# TranslatorETH.net
KiCad netlist of a schematic drawn in EAGLE
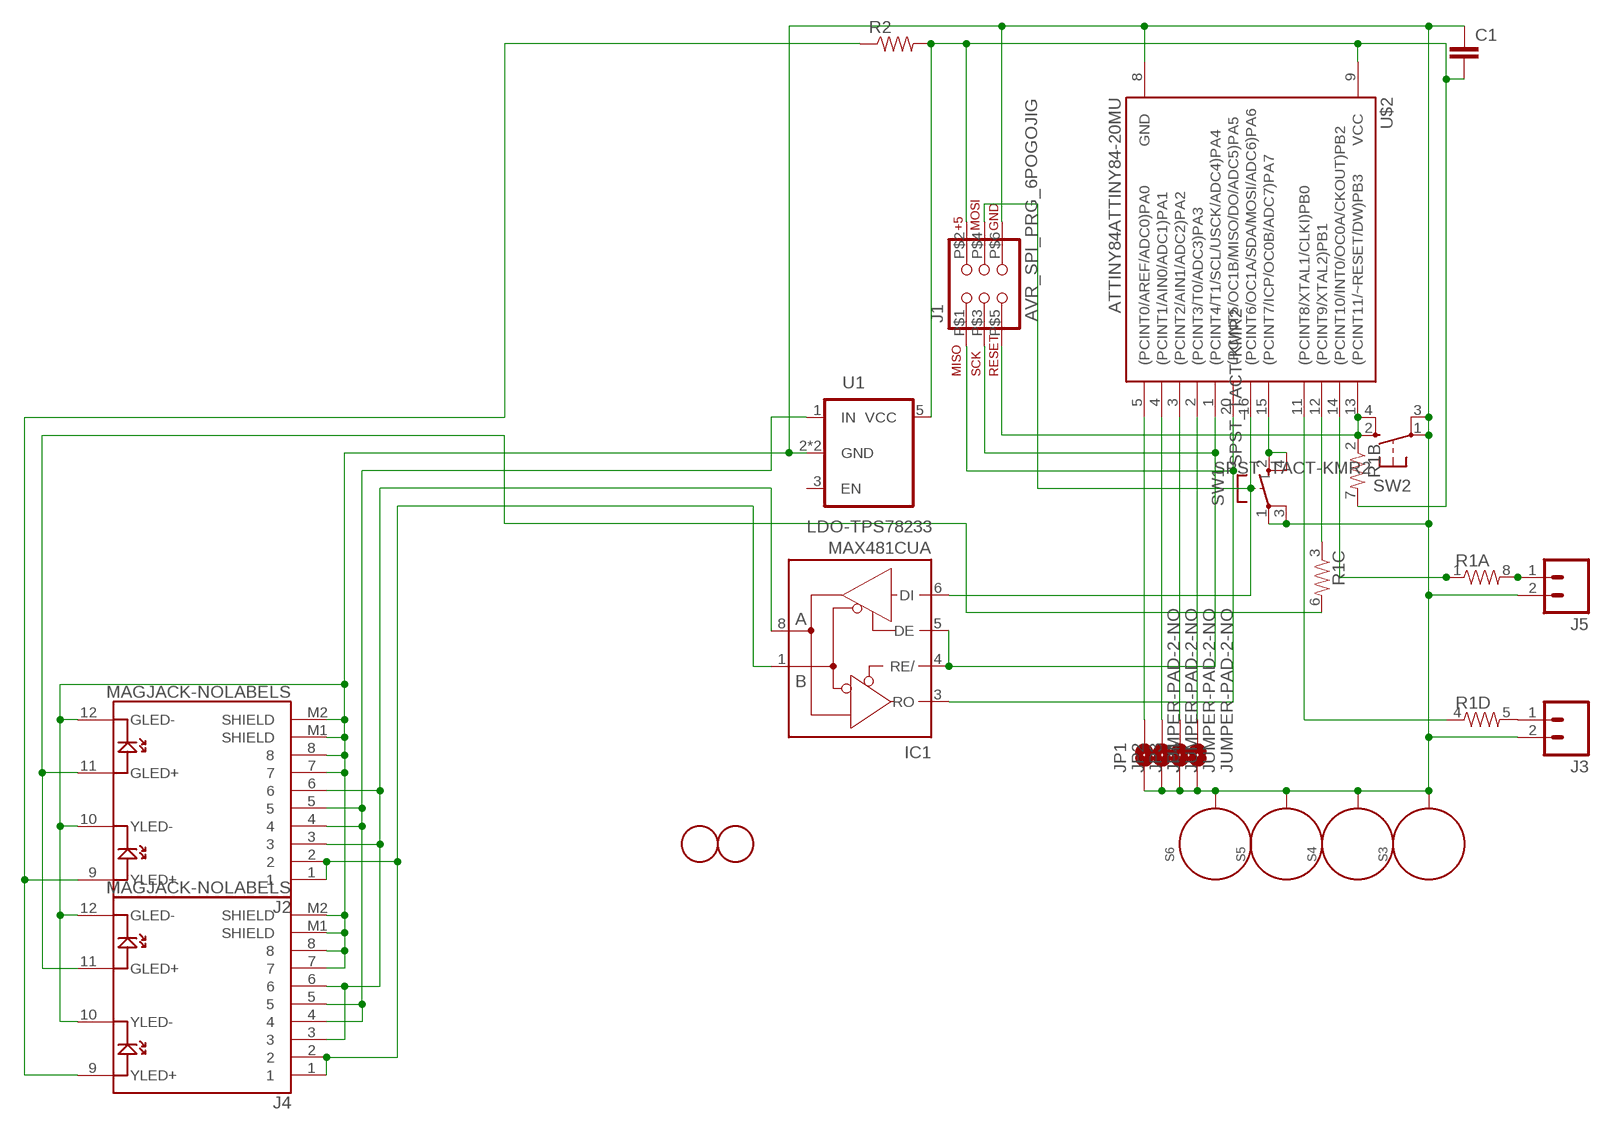
[diagram p0: schematic, sheet 1]

(export (version "E")
  (design (tool "Eeschema 10.0.6"))
  (components
    (comp (ref "C1")
      (value "CAP0805")
      (footprint "eagle-import:0805")
      (libsource (lib "eagle-import") (part "CAP0805"))
    )
    (comp (ref "IC1")
      (value "MAX481CUA")
      (footprint "eagle-import:UMAX8")
      (fields (field (name "MPN") "MAX481CUA+"))
      (libsource (lib "eagle-import") (part "MAX481CUA"))
    )
    (comp (ref "J1")
      (value "AVR_SPI_PRG_6POGOJIG")
      (footprint "eagle-import:2X3_MAX")
      (libsource (lib "eagle-import") (part "AVR_SPI_PRG_6POGOJIG"))
    )
    (comp (ref "J2")
      (value "MAGJACK-NOLABELS")
      (footprint "eagle-import:MAGJACK")
      (libsource (lib "eagle-import") (part "MAGJACK-NOLABELS"))
    )
    (comp (ref "J3")
      (value "M025MM")
      (footprint "eagle-import:SCREWTERMINAL-5MM-2")
      (libsource (lib "eagle-import") (part "M025MM"))
    )
    (comp (ref "J4")
      (value "MAGJACK-NOLABELS")
      (footprint "eagle-import:MAGJACK")
      (libsource (lib "eagle-import") (part "MAGJACK-NOLABELS"))
    )
    (comp (ref "J5")
      (value "M025MM")
      (footprint "eagle-import:SCREWTERMINAL-5MM-2")
      (libsource (lib "eagle-import") (part "M025MM"))
    )
    (comp (ref "JP1")
      (value "JUMPER-PAD-2-NO")
      (footprint "eagle-import:PAD-JUMPER-2-NO_NO_SILK")
      (libsource (lib "eagle-import") (part "JUMPER-PAD-2-NO"))
    )
    (comp (ref "JP2")
      (value "JUMPER-PAD-2-NO")
      (footprint "eagle-import:PAD-JUMPER-2-NO_NO_SILK")
      (libsource (lib "eagle-import") (part "JUMPER-PAD-2-NO"))
    )
    (comp (ref "JP3")
      (value "JUMPER-PAD-2-NO")
      (footprint "eagle-import:PAD-JUMPER-2-NO_NO_SILK")
      (libsource (lib "eagle-import") (part "JUMPER-PAD-2-NO"))
    )
    (comp (ref "JP4")
      (value "JUMPER-PAD-2-NO")
      (footprint "eagle-import:PAD-JUMPER-2-NO_NO_SILK")
      (libsource (lib "eagle-import") (part "JUMPER-PAD-2-NO"))
    )
    (comp (ref "R1")
      (value "RESISTOR-ARRAY0603-ARV")
      (footprint "eagle-import:0603-ARV")
      (libsource (lib "eagle-import") (part "RESISTOR-ARRAY0603-ARV"))
    )
    (comp (ref "R2")
      (value "RESISTOR0805-RES")
      (footprint "eagle-import:0805")
      (libsource (lib "eagle-import") (part "RESISTOR0805-RES"))
    )
    (comp (ref "S3")
      (value "STANDOFF_ELECTRICAL")
      (footprint "eagle-import:STANDOFF-ELECTRICAL")
      (libsource (lib "eagle-import") (part "STANDOFF_ELECTRICAL"))
    )
    (comp (ref "S4")
      (value "STANDOFF_ELECTRICAL")
      (footprint "eagle-import:STANDOFF-ELECTRICAL")
      (libsource (lib "eagle-import") (part "STANDOFF_ELECTRICAL"))
    )
    (comp (ref "S5")
      (value "STANDOFF_ELECTRICAL")
      (footprint "eagle-import:STANDOFF-ELECTRICAL")
      (libsource (lib "eagle-import") (part "STANDOFF_ELECTRICAL"))
    )
    (comp (ref "S6")
      (value "STANDOFF_ELECTRICAL")
      (footprint "eagle-import:STANDOFF-ELECTRICAL")
      (libsource (lib "eagle-import") (part "STANDOFF_ELECTRICAL"))
    )
    (comp (ref "SW1")
      (value "SPST_TACT-KMR2")
      (footprint "eagle-import:KMR2")
      (libsource (lib "eagle-import") (part "SPST_TACT-KMR2"))
    )
    (comp (ref "SW2")
      (value "SPST_TACT-KMR2")
      (footprint "eagle-import:KMR2")
      (libsource (lib "eagle-import") (part "SPST_TACT-KMR2"))
    )
    (comp (ref "U$2")
      (value "ATTINY84ATTINY84-20MU")
      (footprint "eagle-import:QFN20")
      (libsource (lib "eagle-import") (part "ATTINY84ATTINY84-20MU"))
    )
    (comp (ref "U$3")
      (value "FIDUCIAL")
      (footprint "eagle-import:FIDUCIAL_1MM")
      (libsource (lib "eagle-import") (part "FIDUCIAL"))
    )
    (comp (ref "U$4")
      (value "FIDUCIAL")
      (footprint "eagle-import:FIDUCIAL_1MM")
      (libsource (lib "eagle-import") (part "FIDUCIAL"))
    )
    (comp (ref "U1")
      (value "LDO-TPS78233")
      (footprint "eagle-import:SOT23-5")
      (libsource (lib "eagle-import") (part "LDO-TPS78233"))
    )
  )
  (nets
    (net (code "1") (name "Net-(IC1A-A)") (class "Default")
      (node (ref "IC1") (pin "8") (pinfunction "A_8") (pintype "passive"))
      (node (ref "J2") (pin "3") (pinfunction "3_3") (pintype "bidirectional"))
      (node (ref "J2") (pin "6") (pinfunction "6_6") (pintype "bidirectional"))
      (node (ref "J4") (pin "3") (pinfunction "3_3") (pintype "bidirectional"))
      (node (ref "J4") (pin "6") (pinfunction "6_6") (pintype "bidirectional"))
    )
    (net (code "2") (name "Net-(IC1A-B)") (class "Default")
      (node (ref "IC1") (pin "1") (pinfunction "B_1") (pintype "passive"))
      (node (ref "J2") (pin "1") (pinfunction "1_1") (pintype "bidirectional"))
      (node (ref "J2") (pin "2") (pinfunction "2_2") (pintype "bidirectional"))
      (node (ref "J4") (pin "1") (pinfunction "1_1") (pintype "bidirectional"))
      (node (ref "J4") (pin "2") (pinfunction "2_2") (pintype "bidirectional"))
    )
    (net (code "3") (name "Net-(IC1A-DE)") (class "Default")
      (node (ref "IC1") (pin "4") (pinfunction "RE/_4") (pintype "input"))
      (node (ref "IC1") (pin "5") (pinfunction "DE_5") (pintype "input"))
      (node (ref "J1") (pin "P$3") (pinfunction "SCK_P$3") (pintype "passive"))
      (node (ref "U$2") (pin "1") (pinfunction "(PCINT4/T1/SCL/USCK/ADC4)PA4_1") (pintype "bidirectional"))
    )
    (net (code "4") (name "Net-(IC1A-DI)") (class "Default")
      (node (ref "IC1") (pin "6") (pinfunction "DI_6") (pintype "input"))
      (node (ref "J1") (pin "P$4") (pinfunction "MOSI_P$4") (pintype "passive"))
      (node (ref "U$2") (pin "16") (pinfunction "(PCINT6/OC1A/SDA/MOSI/ADC6)PA6_16") (pintype "bidirectional"))
    )
    (net (code "5") (name "Net-(IC1A-RO)") (class "Default")
      (node (ref "IC1") (pin "3") (pinfunction "RO_3") (pintype "output"))
      (node (ref "J1") (pin "P$1") (pinfunction "MISO_P$1") (pintype "passive"))
      (node (ref "U$2") (pin "20") (pinfunction "(PCINT5/OC1B/MISO/DO/ADC5)PA5_20") (pintype "bidirectional"))
    )
    (net (code "6") (name "Net-(J1-GND)") (class "Default")
      (node (ref "C1") (pin "1") (pinfunction "1_1") (pintype "passive"))
      (node (ref "J1") (pin "P$6") (pinfunction "GND_P$6") (pintype "passive"))
      (node (ref "J2") (pin "10") (pinfunction "YLED-_10") (pintype "bidirectional"))
      (node (ref "J2") (pin "12") (pinfunction "GLED-_12") (pintype "bidirectional"))
      (node (ref "J2") (pin "7") (pinfunction "7_7") (pintype "bidirectional"))
      (node (ref "J2") (pin "8") (pinfunction "8_8") (pintype "bidirectional"))
      (node (ref "J2") (pin "M1") (pinfunction "SHIELD_M1") (pintype "bidirectional"))
      (node (ref "J2") (pin "M2") (pinfunction "SHIELD_M2") (pintype "bidirectional"))
      (node (ref "J3") (pin "2") (pinfunction "2_2") (pintype "passive"))
      (node (ref "J4") (pin "10") (pinfunction "YLED-_10") (pintype "bidirectional"))
      (node (ref "J4") (pin "12") (pinfunction "GLED-_12") (pintype "bidirectional"))
      (node (ref "J4") (pin "7") (pinfunction "7_7") (pintype "bidirectional"))
      (node (ref "J4") (pin "8") (pinfunction "8_8") (pintype "bidirectional"))
      (node (ref "J4") (pin "M1") (pinfunction "SHIELD_M1") (pintype "bidirectional"))
      (node (ref "J4") (pin "M2") (pinfunction "SHIELD_M2") (pintype "bidirectional"))
      (node (ref "J5") (pin "2") (pinfunction "2_2") (pintype "passive"))
      (node (ref "JP1") (pin "1") (pinfunction "1_1") (pintype "passive"))
      (node (ref "JP2") (pin "1") (pinfunction "1_1") (pintype "passive"))
      (node (ref "JP3") (pin "1") (pinfunction "1_1") (pintype "passive"))
      (node (ref "JP4") (pin "1") (pinfunction "1_1") (pintype "passive"))
      (node (ref "S3") (pin "P1") (pinfunction "P$1_P1") (pintype "bidirectional"))
      (node (ref "S4") (pin "P1") (pinfunction "P$1_P1") (pintype "bidirectional"))
      (node (ref "S5") (pin "P1") (pinfunction "P$1_P1") (pintype "bidirectional"))
      (node (ref "S6") (pin "P1") (pinfunction "P$1_P1") (pintype "bidirectional"))
      (node (ref "SW1") (pin "1") (pinfunction "P_1") (pintype "passive"))
      (node (ref "SW1") (pin "3") (pinfunction "P1_3") (pintype "passive"))
      (node (ref "SW2") (pin "1") (pinfunction "P_1") (pintype "passive"))
      (node (ref "SW2") (pin "3") (pinfunction "P1_3") (pintype "passive"))
      (node (ref "U$2") (pin "8") (pinfunction "GND_8") (pintype "bidirectional"))
      (node (ref "U1") (pin "2") (pinfunction "GND_2") (pintype "input"))
      (node (ref "U1") (pin "4") (pinfunction "GND_4") (pintype "input"))
    )
    (net (code "7") (name "Net-(J1-RESET)") (class "Default")
      (node (ref "J1") (pin "P$5") (pinfunction "RESET_P$5") (pintype "passive"))
      (node (ref "R1") (pin "2") (pinfunction "1_2") (pintype "passive"))
      (node (ref "SW2") (pin "2") (pinfunction "S_2") (pintype "passive"))
      (node (ref "SW2") (pin "4") (pinfunction "S1_4") (pintype "passive"))
      (node (ref "U$2") (pin "13") (pinfunction "(PCINT11/~{RESET/DW})PB3_13") (pintype "bidirectional"))
    )
    (net (code "8") (name "Net-(J1-VIN)") (class "Default")
      (node (ref "C1") (pin "2") (pinfunction "2_2") (pintype "passive"))
      (node (ref "J1") (pin "P$2") (pinfunction "VIN_P$2") (pintype "passive"))
      (node (ref "R1") (pin "7") (pinfunction "2_7") (pintype "passive"))
      (node (ref "R2") (pin "2") (pinfunction "2_2") (pintype "passive"))
      (node (ref "U$2") (pin "9") (pinfunction "VCC_9") (pintype "bidirectional"))
      (node (ref "U1") (pin "5") (pinfunction "VCC_5") (pintype "power_in"))
    )
    (net (code "9") (name "Net-(J2-GLED+)") (class "Default")
      (node (ref "J2") (pin "11") (pinfunction "GLED+_11") (pintype "bidirectional"))
      (node (ref "J4") (pin "11") (pinfunction "GLED+_11") (pintype "bidirectional"))
      (node (ref "R1") (pin "6") (pinfunction "2_6") (pintype "passive"))
    )
    (net (code "10") (name "Net-(J2-YLED+)") (class "Default")
      (node (ref "J2") (pin "9") (pinfunction "YLED+_9") (pintype "bidirectional"))
      (node (ref "J4") (pin "9") (pinfunction "YLED+_9") (pintype "bidirectional"))
      (node (ref "R2") (pin "1") (pinfunction "1_1") (pintype "passive"))
    )
    (net (code "11") (name "Net-(R1A-2)") (class "Default")
      (node (ref "J5") (pin "1") (pinfunction "1_1") (pintype "passive"))
      (node (ref "R1") (pin "8") (pinfunction "2_8") (pintype "passive"))
    )
    (net (code "12") (name "Net-(R1C-1)") (class "Default")
      (node (ref "R1") (pin "3") (pinfunction "1_3") (pintype "passive"))
      (node (ref "U$2") (pin "12") (pinfunction "(PCINT9/XTAL2)PB1_12") (pintype "bidirectional"))
    )
    (net (code "13") (name "Net-(R1D-1)") (class "Default")
      (node (ref "R1") (pin "4") (pinfunction "1_4") (pintype "passive"))
      (node (ref "U$2") (pin "11") (pinfunction "(PCINT8/XTAL1/CLKI)PB0_11") (pintype "bidirectional"))
    )
    (net (code "14") (name "Net-(R1D-2)") (class "Default")
      (node (ref "J3") (pin "1") (pinfunction "1_1") (pintype "passive"))
      (node (ref "R1") (pin "5") (pinfunction "2_5") (pintype "passive"))
    )
    (net (code "15") (name "Net-(SW1-S)") (class "Default")
      (node (ref "SW1") (pin "2") (pinfunction "S_2") (pintype "passive"))
      (node (ref "SW1") (pin "4") (pinfunction "S1_4") (pintype "passive"))
      (node (ref "U$2") (pin "15") (pinfunction "(PCINT7/ICP/OC0B/ADC7)PA7_15") (pintype "bidirectional"))
    )
    (net (code "16") (name "Net-(U$2-(PCINT0{slash}AREF{slash}ADC0)PA0)") (class "Default")
      (node (ref "JP1") (pin "2") (pinfunction "2_2") (pintype "passive"))
      (node (ref "U$2") (pin "5") (pinfunction "(PCINT0/AREF/ADC0)PA0_5") (pintype "bidirectional"))
    )
    (net (code "17") (name "Net-(U$2-(PCINT1{slash}AIN0{slash}ADC1)PA1)") (class "Default")
      (node (ref "JP2") (pin "2") (pinfunction "2_2") (pintype "passive"))
      (node (ref "U$2") (pin "4") (pinfunction "(PCINT1/AIN0/ADC1)PA1_4") (pintype "bidirectional"))
    )
    (net (code "18") (name "Net-(U$2-(PCINT2{slash}AIN1{slash}ADC2)PA2)") (class "Default")
      (node (ref "JP3") (pin "2") (pinfunction "2_2") (pintype "passive"))
      (node (ref "U$2") (pin "3") (pinfunction "(PCINT2/AIN1/ADC2)PA2_3") (pintype "bidirectional"))
    )
    (net (code "19") (name "Net-(U$2-(PCINT3{slash}T0{slash}ADC3)PA3)") (class "Default")
      (node (ref "JP4") (pin "2") (pinfunction "2_2") (pintype "passive"))
      (node (ref "U$2") (pin "2") (pinfunction "(PCINT3/T0/ADC3)PA3_2") (pintype "bidirectional"))
    )
    (net (code "20") (name "Net-(U$2-(PCINT10{slash}INT0{slash}OC0A{slash}CKOUT)PB2)") (class "Default")
      (node (ref "R1") (pin "1") (pinfunction "1_1") (pintype "passive"))
      (node (ref "U$2") (pin "14") (pinfunction "(PCINT10/INT0/OC0A/CKOUT)PB2_14") (pintype "bidirectional"))
    )
    (net (code "21") (name "Net-(U1-IN)") (class "Default")
      (node (ref "J2") (pin "4") (pinfunction "4_4") (pintype "bidirectional"))
      (node (ref "J2") (pin "5") (pinfunction "5_5") (pintype "bidirectional"))
      (node (ref "J4") (pin "4") (pinfunction "4_4") (pintype "bidirectional"))
      (node (ref "J4") (pin "5") (pinfunction "5_5") (pintype "bidirectional"))
      (node (ref "U1") (pin "1") (pinfunction "IN_1") (pintype "input"))
    )
    (net (code "22") (name "unconnected-(U1-EN-Pad3)") (class "Default")
      (node (ref "U1") (pin "3") (pinfunction "EN_3") (pintype "input"))
    )
  )
)
